# Sheet1.net
KiCad netlist of a schematic drawn in Altium Designer
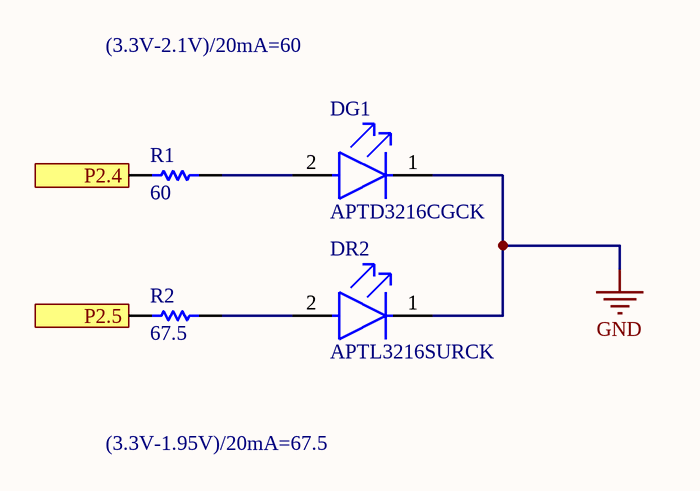
[diagram p0: Sheet1.SchDoc]

(export (version "E")
  (design (tool "Eeschema 10.0.6"))
  (components
    (comp (ref "DG1")
      (value "APTD3216CGCK")
      (footprint "FP-APTD3216CGCK-MFG")
      (description "LED GREEN CLEAR 2SMD")
      (libsource (lib "Altium Content Vault") (part "8706943c75ba83719d021d2fdc84c58"))
    )
    (comp (ref "DR2")
      (value "APTL3216SURCK")
      (footprint "FP-APTL3216SURCK-MFG")
      (description "LED RED CLEAR CHIP SMD")
      (fields
        (field (name "MANUFACTURER") "Kingbright")
        (field (name "OCTOPART") "https://octopart.com/aptl3216surck-kingbright-5355676")
      )
      (libsource (lib "Altium Content Vault") (part "8706943c75ba83719d021d2fdc84c58"))
    )
    (comp (ref "R1")
      (value "60")
      (footprint "RESC2013X70X40ML20T20")
      (fields (field (name "PART NUMBER") "ERJ-6ENF66R5V") (field (name "MANUFACTURER") "Panasonic"))
      (libsource (lib "Altium Content Vault") (part "RES"))
    )
    (comp (ref "R2")
      (value "67.5")
      (footprint "RESC2013X70X40ML20T20")
      (fields (field (name "PART NUMBER") "ERJ-6ENF66R5V") (field (name "MANUFACTURER") "Panasonic"))
      (libsource (lib "Altium Content Vault") (part "RES"))
    )
  )
  (nets
    (net (code "1") (name "/P2.4") (class "Default")
      (node (ref "R1") (pin "1") (pinfunction "1_1") (pintype "passive"))
    )
    (net (code "2") (name "/P2.5") (class "Default")
      (node (ref "R2") (pin "1") (pinfunction "1_1") (pintype "passive"))
    )
    (net (code "3") (name "GND") (class "Default")
      (node (ref "DG1") (pin "1") (pinfunction "C_1") (pintype "passive"))
      (node (ref "DR2") (pin "1") (pinfunction "C_1") (pintype "passive"))
    )
    (net (code "4") (name "Net-(DG1-A)") (class "Default")
      (node (ref "DG1") (pin "2") (pinfunction "A_2") (pintype "passive"))
      (node (ref "R1") (pin "2") (pinfunction "2_2") (pintype "passive"))
    )
    (net (code "5") (name "Net-(DR2-A)") (class "Default")
      (node (ref "DR2") (pin "2") (pinfunction "A_2") (pintype "passive"))
      (node (ref "R2") (pin "2") (pinfunction "2_2") (pintype "passive"))
    )
  )
)
